# power.net
KiCad netlist of a schematic drawn in Altium Designer
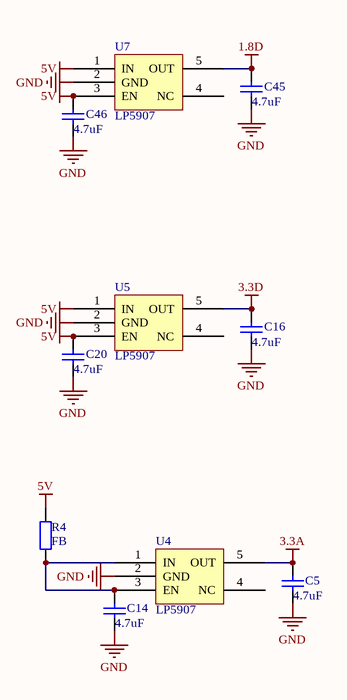
[diagram p0: power.SchDoc]

(export (version "E")
  (design (tool "Eeschema 10.0.6"))
  (components
    (comp (ref "C5")
      (value "4.7uF")
      (footprint "0603L")
      (description "Capacitor")
      (fields (field (name "PUBLISHER") "Altium Limited"))
      (libsource (lib "RTC6705") (part "Cap"))
    )
    (comp (ref "C14")
      (value "4.7uF")
      (footprint "0603L")
      (description "Capacitor")
      (fields (field (name "PUBLISHER") "Altium Limited"))
      (libsource (lib "RTC6705") (part "Cap"))
    )
    (comp (ref "C16")
      (value "4.7uF")
      (footprint "0603L")
      (description "Capacitor")
      (fields (field (name "PUBLISHER") "Altium Limited"))
      (libsource (lib "RTC6705") (part "Cap"))
    )
    (comp (ref "C20")
      (value "4.7uF")
      (footprint "0603L")
      (description "Capacitor")
      (fields (field (name "PUBLISHER") "Altium Limited"))
      (libsource (lib "RTC6705") (part "Cap"))
    )
    (comp (ref "C45")
      (value "4.7uF")
      (footprint "0603L")
      (description "Capacitor")
      (fields (field (name "PUBLISHER") "Altium Limited"))
      (libsource (lib "RTC6705") (part "Cap"))
    )
    (comp (ref "C46")
      (value "4.7uF")
      (footprint "0603L")
      (description "Capacitor")
      (fields (field (name "PUBLISHER") "Altium Limited"))
      (libsource (lib "RTC6705") (part "Cap"))
    )
    (comp (ref "R4")
      (value "FB")
      (footprint "0603L")
      (description "Resistor")
      (fields (field (name "PUBLISHER") "Altium Limited"))
      (libsource (lib "Miscellaneous Devices") (part "Res2"))
    )
    (comp (ref "U4") (value "LP5907") (footprint "SOT23-5") (libsource (lib "RTC6705") (part "LP5907")))
    (comp (ref "U5") (value "LP5907") (footprint "SOT23-5") (libsource (lib "RTC6705") (part "LP5907")))
    (comp (ref "U7") (value "LP5907") (footprint "SOT23-5") (libsource (lib "RTC6705") (part "LP5907")))
  )
  (nets
    (net (code "1") (name "1.8D") (class "Default")
      (node (ref "C45") (pin "2") (pinfunction "2_2") (pintype "passive"))
      (node (ref "U7") (pin "5") (pinfunction "OUT_5") (pintype "passive"))
    )
    (net (code "2") (name "3.3A") (class "Default")
      (node (ref "C5") (pin "2") (pinfunction "2_2") (pintype "passive"))
      (node (ref "U4") (pin "5") (pinfunction "OUT_5") (pintype "passive"))
    )
    (net (code "3") (name "3.3D") (class "Default")
      (node (ref "C16") (pin "2") (pinfunction "2_2") (pintype "passive"))
      (node (ref "U5") (pin "5") (pinfunction "OUT_5") (pintype "passive"))
    )
    (net (code "4") (name "5V") (class "Default")
      (node (ref "C20") (pin "2") (pinfunction "2_2") (pintype "passive"))
      (node (ref "C46") (pin "2") (pinfunction "2_2") (pintype "passive"))
      (node (ref "R4") (pin "2") (pinfunction "2_2") (pintype "passive"))
      (node (ref "U5") (pin "1") (pinfunction "IN_1") (pintype "passive"))
      (node (ref "U5") (pin "3") (pinfunction "EN_3") (pintype "passive"))
      (node (ref "U7") (pin "1") (pinfunction "IN_1") (pintype "passive"))
      (node (ref "U7") (pin "3") (pinfunction "EN_3") (pintype "passive"))
    )
    (net (code "5") (name "GND") (class "Default")
      (node (ref "C14") (pin "1") (pinfunction "1_1") (pintype "passive"))
      (node (ref "C16") (pin "1") (pinfunction "1_1") (pintype "passive"))
      (node (ref "C20") (pin "1") (pinfunction "1_1") (pintype "passive"))
      (node (ref "C45") (pin "1") (pinfunction "1_1") (pintype "passive"))
      (node (ref "C46") (pin "1") (pinfunction "1_1") (pintype "passive"))
      (node (ref "C5") (pin "1") (pinfunction "1_1") (pintype "passive"))
      (node (ref "U4") (pin "2") (pinfunction "GND_2") (pintype "passive"))
      (node (ref "U5") (pin "2") (pinfunction "GND_2") (pintype "passive"))
      (node (ref "U7") (pin "2") (pinfunction "GND_2") (pintype "passive"))
    )
    (net (code "6") (name "Net-(U4-EN)") (class "Default")
      (node (ref "C14") (pin "2") (pinfunction "2_2") (pintype "passive"))
      (node (ref "R4") (pin "1") (pinfunction "1_1") (pintype "passive"))
      (node (ref "U4") (pin "1") (pinfunction "IN_1") (pintype "passive"))
      (node (ref "U4") (pin "3") (pinfunction "EN_3") (pintype "passive"))
    )
    (net (code "7") (name "unconnected-(U4-NC-Pad4)") (class "Default")
      (node (ref "U4") (pin "4") (pinfunction "NC_4") (pintype "passive"))
    )
    (net (code "8") (name "unconnected-(U5-NC-Pad4)") (class "Default")
      (node (ref "U5") (pin "4") (pinfunction "NC_4") (pintype "passive"))
    )
    (net (code "9") (name "unconnected-(U7-NC-Pad4)") (class "Default")
      (node (ref "U7") (pin "4") (pinfunction "NC_4") (pintype "passive"))
    )
  )
)
